# RS485_RS232_Sheet.net
KiCad netlist of a schematic drawn in Altium Designer
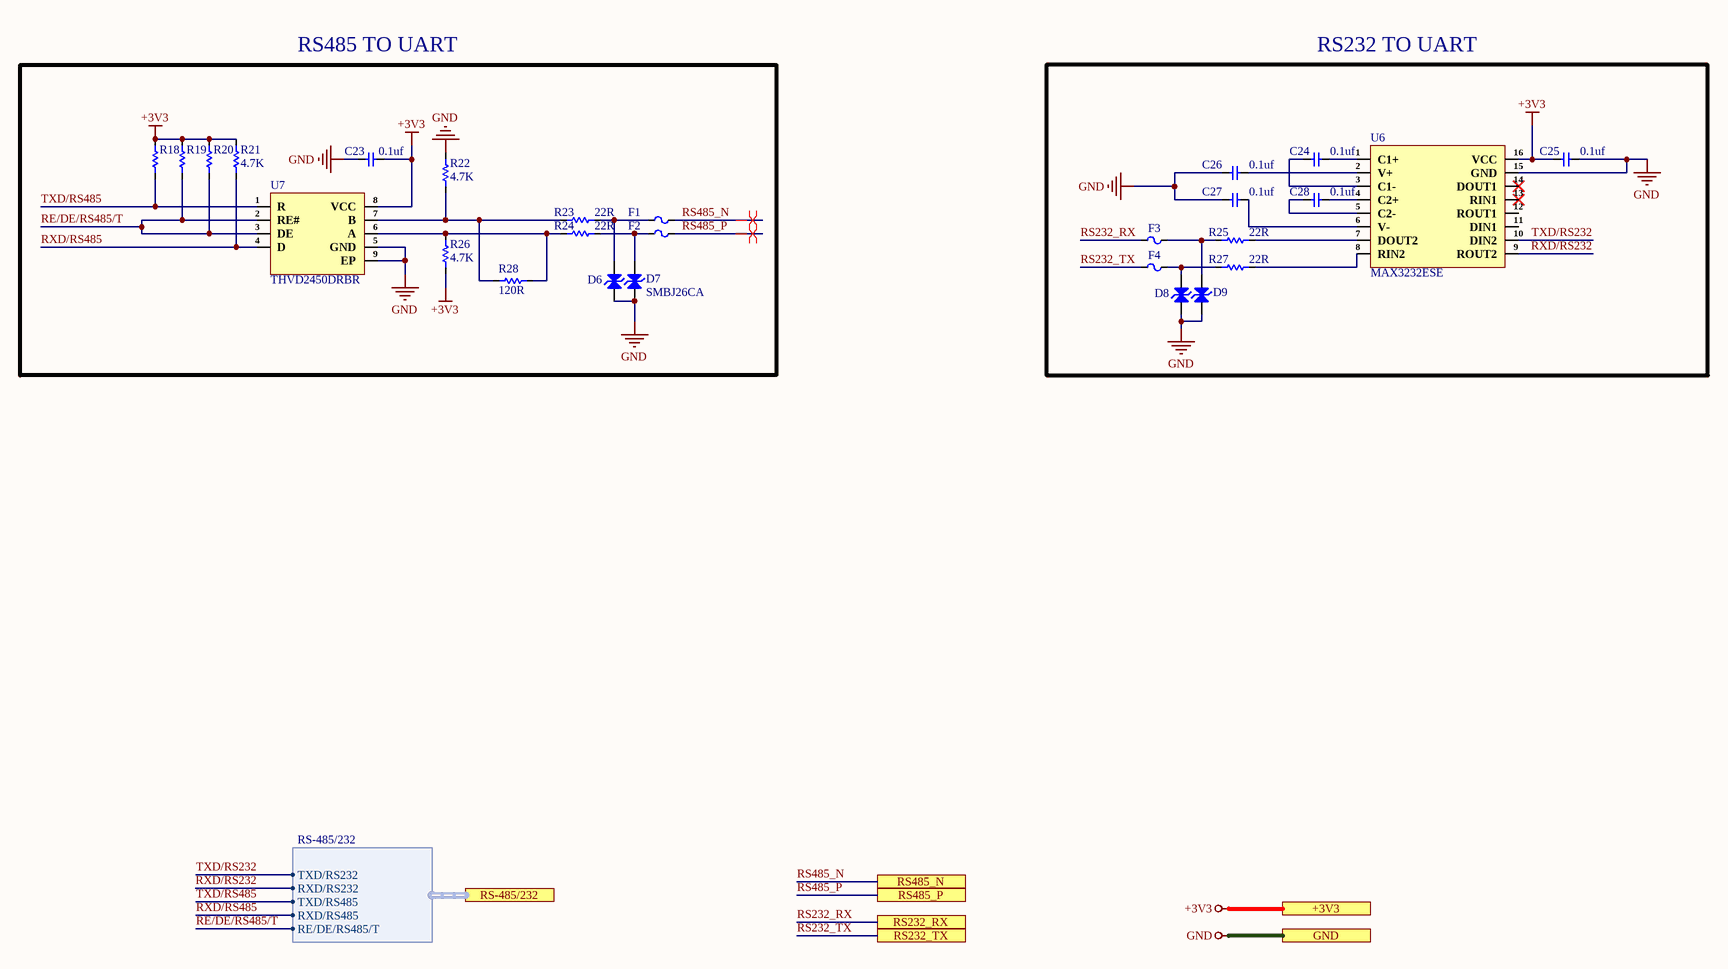
[diagram p0: RS485_RS232_Sheet.SchDoc]

(export (version "E")
  (design (tool "Eeschema 10.0.6"))
  (components
    (comp (ref "C23")
      (value "0.1uf")
      (footprint "Cap-0402")
      (description "CAP CER 0.1UF 100V X5R 0402")
      (fields
        (field (name "MANUFACTURER") "Murata")
        (field (name "MANUFACTURER PART NUMBER") "GRM155R62A104KE14D")
      )
      (libsource (lib "eSpark Libraries") (part "GRM155R62A104KE14D"))
    )
    (comp (ref "C24")
      (value "0.1uf")
      (footprint "Cap-0402")
      (description "CAP CER 0.1UF 100V X5R 0402")
      (fields
        (field (name "MANUFACTURER") "Murata")
        (field (name "MANUFACTURER PART NUMBER") "GRM155R62A104KE14D")
      )
      (libsource (lib "eSpark Libraries") (part "GRM155R62A104KE14D"))
    )
    (comp (ref "C25")
      (value "0.1uf")
      (footprint "Cap-0402")
      (description "CAP CER 0.1UF 100V X5R 0402")
      (fields
        (field (name "MANUFACTURER") "Murata")
        (field (name "MANUFACTURER PART NUMBER") "GRM155R62A104KE14D")
      )
      (libsource (lib "eSpark Libraries") (part "GRM155R62A104KE14D"))
    )
    (comp (ref "C26")
      (value "0.1uf")
      (footprint "Cap-0402")
      (description "CAP CER 0.1UF 100V X5R 0402")
      (fields
        (field (name "MANUFACTURER") "Murata")
        (field (name "MANUFACTURER PART NUMBER") "GRM155R62A104KE14D")
      )
      (libsource (lib "eSpark Libraries") (part "GRM155R62A104KE14D"))
    )
    (comp (ref "C27")
      (value "0.1uf")
      (footprint "Cap-0402")
      (description "CAP CER 0.1UF 100V X5R 0402")
      (fields
        (field (name "MANUFACTURER") "Murata")
        (field (name "MANUFACTURER PART NUMBER") "GRM155R62A104KE14D")
      )
      (libsource (lib "eSpark Libraries") (part "GRM155R62A104KE14D"))
    )
    (comp (ref "C28")
      (value "0.1uf")
      (footprint "Cap-0402")
      (description "CAP CER 0.1UF 100V X5R 0402")
      (fields
        (field (name "MANUFACTURER") "Murata")
        (field (name "MANUFACTURER PART NUMBER") "GRM155R62A104KE14D")
      )
      (libsource (lib "eSpark Libraries") (part "GRM155R62A104KE14D"))
    )
    (comp (ref "D6")
      (value "SMBJ26CA")
      (footprint "SMB Bi Directional")
      (description "SMB(DO-214AA) TVS ROHS")
      (fields (field (name "MANUFACTURER") "MSKSEMI") (field (name "LCSC PART NUMBER") "C5331111"))
      (libsource (lib "eSpark Libraries") (part "SMBJ26CA"))
    )
    (comp (ref "D7")
      (value "SMBJ26CA")
      (footprint "SMB Bi Directional")
      (description "SMB(DO-214AA) TVS ROHS")
      (fields (field (name "MANUFACTURER") "MSKSEMI") (field (name "LCSC PART NUMBER") "C5331111"))
      (libsource (lib "eSpark Libraries") (part "SMBJ26CA"))
    )
    (comp (ref "D8")
      (value "SMBJ26CA")
      (footprint "SMB Bi Directional")
      (description "SMB(DO-214AA) TVS ROHS")
      (fields (field (name "MANUFACTURER") "MSKSEMI") (field (name "LCSC PART NUMBER") "C5331111"))
      (libsource (lib "eSpark Libraries") (part "SMBJ26CA"))
    )
    (comp (ref "D9")
      (value "SMBJ26CA")
      (footprint "SMB Bi Directional")
      (description "SMB(DO-214AA) TVS ROHS")
      (fields (field (name "MANUFACTURER") "MSKSEMI") (field (name "LCSC PART NUMBER") "C5331111"))
      (libsource (lib "eSpark Libraries") (part "SMBJ26CA"))
    )
    (comp (ref "F1")
      (value "SMD0805P020TF")
      (footprint "Fuse-0805")
      (description "9V 200mA 100A 500mA 0805 Resettable Fuses ROHS")
      (fields (field (name "MANUFACTURER") "RUILON") (field (name "LCSC PART NUMBER") "C20976"))
      (libsource (lib "eSpark_centralized_Library(2022)") (part "SMD0805P020TF"))
    )
    (comp (ref "F2")
      (value "SMD0805P020TF")
      (footprint "Fuse-0805")
      (description "9V 200mA 100A 500mA 0805 Resettable Fuses ROHS")
      (fields (field (name "MANUFACTURER") "RUILON") (field (name "LCSC PART NUMBER") "C20976"))
      (libsource (lib "eSpark_centralized_Library(2022)") (part "SMD0805P020TF"))
    )
    (comp (ref "F3")
      (value "SMD0805P020TF")
      (footprint "Fuse-0805")
      (description "9V 200mA 100A 500mA 0805 Resettable Fuses ROHS")
      (fields (field (name "MANUFACTURER") "RUILON") (field (name "LCSC PART NUMBER") "C20976"))
      (libsource (lib "eSpark Libraries") (part "SMD0805P020TF"))
    )
    (comp (ref "F4")
      (value "SMD0805P020TF")
      (footprint "Fuse-0805")
      (description "9V 200mA 100A 500mA 0805 Resettable Fuses ROHS")
      (fields (field (name "MANUFACTURER") "RUILON") (field (name "LCSC PART NUMBER") "C20976"))
      (libsource (lib "eSpark Libraries") (part "SMD0805P020TF"))
    )
    (comp (ref "R18")
      (value "4.7K")
      (footprint "Res-0402")
      (description "RES 4.7K OHM 1% 1/16W 0402")
      (fields
        (field (name "MANUFACTURER") "Yageo")
        (field (name "MANUFACTURER PART NUMBER") "RC0402FR-074K7L")
      )
      (libsource (lib "eSpark Libraries") (part "RC0402FR-074K7L"))
    )
    (comp (ref "R19")
      (value "4.7K")
      (footprint "Res-0402")
      (description "RES 4.7K OHM 1% 1/16W 0402")
      (fields
        (field (name "MANUFACTURER") "Yageo")
        (field (name "MANUFACTURER PART NUMBER") "RC0402FR-074K7L")
      )
      (libsource (lib "eSpark Libraries") (part "RC0402FR-074K7L"))
    )
    (comp (ref "R20")
      (value "4.7K")
      (footprint "Res-0402")
      (description "RES 4.7K OHM 1% 1/16W 0402")
      (fields
        (field (name "MANUFACTURER") "Yageo")
        (field (name "MANUFACTURER PART NUMBER") "RC0402FR-074K7L")
      )
      (libsource (lib "eSpark Libraries") (part "RC0402FR-074K7L"))
    )
    (comp (ref "R21")
      (value "4.7K")
      (footprint "Res-0402")
      (description "RES 4.7K OHM 1% 1/16W 0402")
      (fields
        (field (name "MANUFACTURER") "Yageo")
        (field (name "MANUFACTURER PART NUMBER") "RC0402FR-074K7L")
      )
      (libsource (lib "eSpark Libraries") (part "RC0402FR-074K7L"))
    )
    (comp (ref "R22")
      (value "4.7K")
      (footprint "Res-0402")
      (description "RES 4.7K OHM 1% 1/16W 0402")
      (fields
        (field (name "MANUFACTURER") "Yageo")
        (field (name "MANUFACTURER PART NUMBER") "RC0402FR-074K7L")
      )
      (libsource (lib "eSpark Libraries") (part "RC0402FR-074K7L"))
    )
    (comp (ref "R23")
      (value "22R")
      (footprint "Res-0201")
      (description "RES 22 OHM 1% 1/20W 0201")
      (fields
        (field (name "MANUFACTURER") "Yageo")
        (field (name "MANUFACTURER PART NUMBER") "RC0201FR-0722RL")
      )
      (libsource (lib "eSpark Libraries") (part "RC0201FR-0722RL"))
    )
    (comp (ref "R24")
      (value "22R")
      (footprint "Res-0201")
      (description "RES 22 OHM 1% 1/20W 0201")
      (fields
        (field (name "MANUFACTURER") "Yageo")
        (field (name "MANUFACTURER PART NUMBER") "RC0201FR-0722RL")
      )
      (libsource (lib "eSpark Libraries") (part "RC0201FR-0722RL"))
    )
    (comp (ref "R25")
      (value "22R")
      (footprint "Res-0201")
      (description "RES 22 OHM 1% 1/20W 0201")
      (fields
        (field (name "MANUFACTURER") "Yageo")
        (field (name "MANUFACTURER PART NUMBER") "RC0201FR-0722RL")
      )
      (libsource (lib "eSpark Libraries") (part "RC0201FR-0722RL"))
    )
    (comp (ref "R26")
      (value "4.7K")
      (footprint "Res-0402")
      (description "RES 4.7K OHM 1% 1/16W 0402")
      (fields
        (field (name "MANUFACTURER") "Yageo")
        (field (name "MANUFACTURER PART NUMBER") "RC0402FR-074K7L")
      )
      (libsource (lib "eSpark Libraries") (part "RC0402FR-074K7L"))
    )
    (comp (ref "R27")
      (value "22R")
      (footprint "Res-0201")
      (description "RES 22 OHM 1% 1/20W 0201")
      (fields
        (field (name "MANUFACTURER") "Yageo")
        (field (name "MANUFACTURER PART NUMBER") "RC0201FR-0722RL")
      )
      (libsource (lib "eSpark Libraries") (part "RC0201FR-0722RL"))
    )
    (comp (ref "R28")
      (value "120R")
      (footprint "Res-0603")
      (description "RES 120 OHM 5% 1/10W 0603")
      (fields
        (field (name "MANUFACTURER") "Yageo")
        (field (name "MANUFACTURER PART NUMBER") "RC0603JR-07120RL")
      )
      (libsource (lib "eSpark Libraries") (part "RC0603JR-07120RL"))
    )
    (comp (ref "U6")
      (value "MAX3232ESE")
      (footprint "SOP-16")
      (description "250Kbps transceiver 2/2 SOP-16 RS232 ICs ROHS")
      (fields (field (name "MANUFACTURER") "UMW") (field (name "LCSC PART NUMBER") "C2904738"))
      (libsource (lib "eSpark Libraries") (part "MAX3232ESE"))
    )
    (comp (ref "U7")
      (value "THVD2450DRBR")
      (footprint "SON-8-EP(3x3)")
      (description "IC TRANSCEIVER HALF 1/1 8SON")
      (fields (field (name "MANUFACTURER") "Texas Instruments") (field (name "LCSC PART NUMBER") "C2878080"))
      (libsource (lib "eSpark Libraries") (part "THVD2450DRBR"))
    )
  )
  (nets
    (net (code "2") (name "+3V3") (class "Default")
      (node (ref "C23") (pin "2") (pinfunction "2_2") (pintype "passive"))
      (node (ref "C25") (pin "2") (pinfunction "2_2") (pintype "passive"))
      (node (ref "R18") (pin "2") (pinfunction "2_2") (pintype "passive"))
      (node (ref "R19") (pin "2") (pinfunction "2_2") (pintype "passive"))
      (node (ref "R20") (pin "2") (pinfunction "2_2") (pintype "passive"))
      (node (ref "R21") (pin "2") (pinfunction "2_2") (pintype "passive"))
      (node (ref "R26") (pin "1") (pinfunction "1_1") (pintype "passive"))
      (node (ref "U6") (pin "16") (pinfunction "VCC_16") (pintype "passive"))
      (node (ref "U7") (pin "8") (pinfunction "VCC_8") (pintype "passive"))
    )
    (net (code "3") (name "/RE{slash}DE{slash}RS485{slash}T") (class "Default")
      (node (ref "R19") (pin "1") (pinfunction "1_1") (pintype "passive"))
      (node (ref "R20") (pin "1") (pinfunction "1_1") (pintype "passive"))
      (node (ref "U7") (pin "2") (pinfunction "RE#_2") (pintype "passive"))
      (node (ref "U7") (pin "3") (pinfunction "DE_3") (pintype "passive"))
    )
    (net (code "4") (name "/RS232_RX") (class "Default")
      (node (ref "F3") (pin "1") (pinfunction "1_1") (pintype "passive"))
    )
    (net (code "5") (name "/RS232_TX") (class "Default")
      (node (ref "F4") (pin "1") (pinfunction "1_1") (pintype "passive"))
    )
    (net (code "6") (name "/RS485_N") (class "Default")
      (node (ref "F1") (pin "2") (pinfunction "2_2") (pintype "passive"))
    )
    (net (code "7") (name "/RS485_P") (class "Default")
      (node (ref "F2") (pin "2") (pinfunction "2_2") (pintype "passive"))
    )
    (net (code "8") (name "/RXD{slash}RS232") (class "Default")
      (node (ref "U6") (pin "9") (pinfunction "ROUT2_9") (pintype "passive"))
    )
    (net (code "9") (name "/RXD{slash}RS485") (class "Default")
      (node (ref "R21") (pin "1") (pinfunction "1_1") (pintype "passive"))
      (node (ref "U7") (pin "4") (pinfunction "D_4") (pintype "passive"))
    )
    (net (code "10") (name "/TXD{slash}RS232") (class "Default")
      (node (ref "U6") (pin "10") (pinfunction "DIN2_10") (pintype "passive"))
    )
    (net (code "11") (name "/TXD{slash}RS485") (class "Default")
      (node (ref "R18") (pin "1") (pinfunction "1_1") (pintype "passive"))
      (node (ref "U7") (pin "1") (pinfunction "R_1") (pintype "passive"))
    )
    (net (code "13") (name "GND") (class "Default")
      (node (ref "C23") (pin "1") (pinfunction "1_1") (pintype "passive"))
      (node (ref "C25") (pin "1") (pinfunction "1_1") (pintype "passive"))
      (node (ref "C26") (pin "1") (pinfunction "1_1") (pintype "passive"))
      (node (ref "C27") (pin "1") (pinfunction "1_1") (pintype "passive"))
      (node (ref "D6") (pin "1") (pinfunction "A_1") (pintype "passive"))
      (node (ref "D7") (pin "1") (pinfunction "A_1") (pintype "passive"))
      (node (ref "D8") (pin "1") (pinfunction "A_1") (pintype "passive"))
      (node (ref "D9") (pin "1") (pinfunction "A_1") (pintype "passive"))
      (node (ref "R22") (pin "2") (pinfunction "2_2") (pintype "passive"))
      (node (ref "U6") (pin "15") (pinfunction "GND_15") (pintype "passive"))
      (node (ref "U7") (pin "5") (pinfunction "GND_5") (pintype "passive"))
      (node (ref "U7") (pin "9") (pinfunction "EP_9") (pintype "passive"))
    )
    (net (code "14") (name "Net-(D6-K)") (class "Default")
      (node (ref "D6") (pin "2") (pinfunction "K_2") (pintype "passive"))
      (node (ref "F1") (pin "1") (pinfunction "1_1") (pintype "passive"))
      (node (ref "R23") (pin "2") (pinfunction "2_2") (pintype "passive"))
    )
    (net (code "15") (name "Net-(D7-K)") (class "Default")
      (node (ref "D7") (pin "2") (pinfunction "K_2") (pintype "passive"))
      (node (ref "F2") (pin "1") (pinfunction "1_1") (pintype "passive"))
      (node (ref "R24") (pin "2") (pinfunction "2_2") (pintype "passive"))
    )
    (net (code "16") (name "Net-(D8-K)") (class "Default")
      (node (ref "D8") (pin "2") (pinfunction "K_2") (pintype "passive"))
      (node (ref "F4") (pin "2") (pinfunction "2_2") (pintype "passive"))
      (node (ref "R27") (pin "1") (pinfunction "1_1") (pintype "passive"))
    )
    (net (code "17") (name "Net-(D9-K)") (class "Default")
      (node (ref "D9") (pin "2") (pinfunction "K_2") (pintype "passive"))
      (node (ref "F3") (pin "2") (pinfunction "2_2") (pintype "passive"))
      (node (ref "R25") (pin "1") (pinfunction "1_1") (pintype "passive"))
    )
    (net (code "18") (name "Net-(U6-C1+)") (class "Default")
      (node (ref "C24") (pin "1") (pinfunction "1_1") (pintype "passive"))
      (node (ref "U6") (pin "1") (pinfunction "C1+_1") (pintype "passive"))
    )
    (net (code "19") (name "Net-(U6-C1-)") (class "Default")
      (node (ref "C24") (pin "2") (pinfunction "2_2") (pintype "passive"))
      (node (ref "U6") (pin "3") (pinfunction "C1-_3") (pintype "passive"))
    )
    (net (code "20") (name "Net-(U6-C2+)") (class "Default")
      (node (ref "C28") (pin "1") (pinfunction "1_1") (pintype "passive"))
      (node (ref "U6") (pin "4") (pinfunction "C2+_4") (pintype "passive"))
    )
    (net (code "21") (name "Net-(U6-C2-)") (class "Default")
      (node (ref "C28") (pin "2") (pinfunction "2_2") (pintype "passive"))
      (node (ref "U6") (pin "5") (pinfunction "C2-_5") (pintype "passive"))
    )
    (net (code "22") (name "Net-(U6-DOUT2)") (class "Default")
      (node (ref "R25") (pin "2") (pinfunction "2_2") (pintype "passive"))
      (node (ref "U6") (pin "7") (pinfunction "DOUT2_7") (pintype "passive"))
    )
    (net (code "23") (name "Net-(U6-RIN2)") (class "Default")
      (node (ref "R27") (pin "2") (pinfunction "2_2") (pintype "passive"))
      (node (ref "U6") (pin "8") (pinfunction "RIN2_8") (pintype "passive"))
    )
    (net (code "24") (name "Net-(U6-V+)") (class "Default")
      (node (ref "C26") (pin "2") (pinfunction "2_2") (pintype "passive"))
      (node (ref "U6") (pin "2") (pinfunction "V+_2") (pintype "passive"))
    )
    (net (code "25") (name "Net-(U6-V-)") (class "Default")
      (node (ref "C27") (pin "2") (pinfunction "2_2") (pintype "passive"))
      (node (ref "U6") (pin "6") (pinfunction "V-_6") (pintype "passive"))
    )
    (net (code "26") (name "Net-(U7-A)") (class "Default")
      (node (ref "R24") (pin "1") (pinfunction "1_1") (pintype "passive"))
      (node (ref "R26") (pin "2") (pinfunction "2_2") (pintype "passive"))
      (node (ref "R28") (pin "2") (pinfunction "2_2") (pintype "passive"))
      (node (ref "U7") (pin "6") (pinfunction "A_6") (pintype "passive"))
    )
    (net (code "27") (name "Net-(U7-B)") (class "Default")
      (node (ref "R22") (pin "1") (pinfunction "1_1") (pintype "passive"))
      (node (ref "R23") (pin "1") (pinfunction "1_1") (pintype "passive"))
      (node (ref "R28") (pin "1") (pinfunction "1_1") (pintype "passive"))
      (node (ref "U7") (pin "7") (pinfunction "B_7") (pintype "passive"))
    )
    (net (code "28") (name "unconnected-(U6-DIN1-Pad11)") (class "Default")
      (node (ref "U6") (pin "11") (pinfunction "DIN1_11") (pintype "passive"))
    )
    (net (code "29") (name "unconnected-(U6-DOUT1-Pad14)") (class "Default")
      (node (ref "U6") (pin "14") (pinfunction "DOUT1_14") (pintype "passive+no_connect"))
    )
    (net (code "30") (name "unconnected-(U6-RIN1-Pad13)") (class "Default")
      (node (ref "U6") (pin "13") (pinfunction "RIN1_13") (pintype "passive+no_connect"))
    )
    (net (code "31") (name "unconnected-(U6-ROUT1-Pad12)") (class "Default")
      (node (ref "U6") (pin "12") (pinfunction "ROUT1_12") (pintype "passive"))
    )
  )
)
